# SourceFollower_SOT23_Simple.net
KiCad netlist of a schematic drawn in Altium Designer
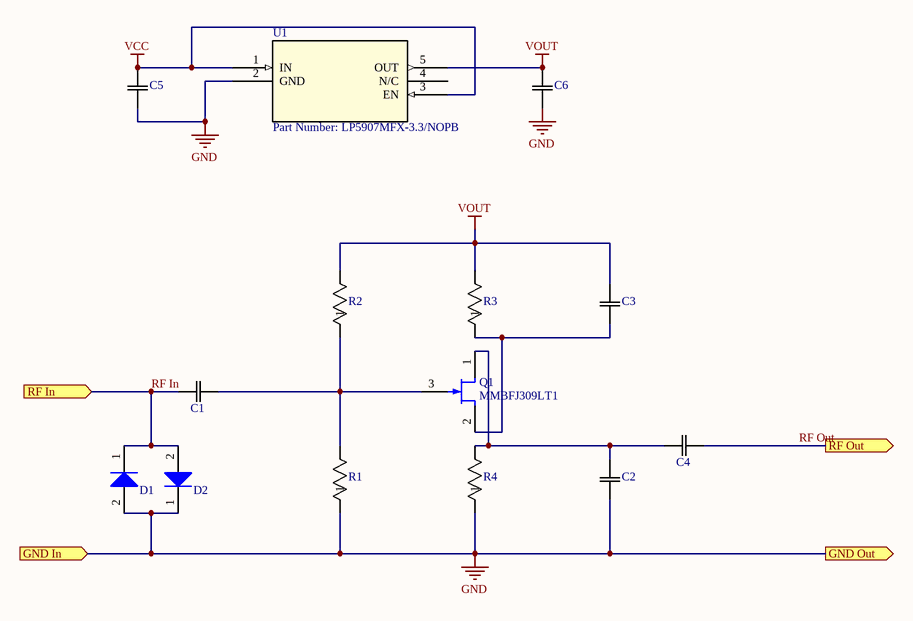
[diagram p0: SourceFollower_SOT23_Simple.SchDoc]

(export (version "E")
  (design (tool "Eeschema 10.0.6"))
  (components
    (comp (ref "C1")
      (value "Part Number: C0201C270J3GACTU")
      (footprint "C0201")
      (description "No Description Available")
      (fields
        (field (name "MANUFACTURER_PART_NUMBER") "C0201C270J3GACTU")
        (field (name "COPYRIGHT") "Copyright (C) 2018 Accelerated Designs. All rights reserved")
      )
      (libsource (lib "0201Capacitor_Yageo") (part "C0201C270J3GACTU"))
    )
    (comp (ref "C2")
      (value "Part Number: C0201C270J3GACTU")
      (footprint "C0201")
      (description "No Description Available")
      (fields
        (field (name "MANUFACTURER_PART_NUMBER") "C0201C270J3GACTU")
        (field (name "COPYRIGHT") "Copyright (C) 2018 Accelerated Designs. All rights reserved")
      )
      (libsource (lib "0201Capacitor_Yageo") (part "C0201C270J3GACTU"))
    )
    (comp (ref "C3")
      (value "Part Number: C0201C270J3GACTU")
      (footprint "C0201")
      (description "No Description Available")
      (fields
        (field (name "MANUFACTURER_PART_NUMBER") "C0201C270J3GACTU")
        (field (name "COPYRIGHT") "Copyright (C) 2018 Accelerated Designs. All rights reserved")
      )
      (libsource (lib "0201Capacitor_Yageo") (part "C0201C270J3GACTU"))
    )
    (comp (ref "C4")
      (value "Part Number: C0201C270J3GACTU")
      (footprint "C0201")
      (description "No Description Available")
      (fields
        (field (name "MANUFACTURER_PART_NUMBER") "C0201C270J3GACTU")
        (field (name "COPYRIGHT") "Copyright (C) 2018 Accelerated Designs. All rights reserved")
      )
      (libsource (lib "0201Capacitor_Yageo") (part "C0201C270J3GACTU"))
    )
    (comp (ref "C5")
      (value "Part Number: CC0402KRX7R6BB104")
      (footprint "YAG_CC0402")
      (description "No Description Available")
      (fields
        (field (name "MANUFACTURER_PART_NUMBER") "CC0402KRX7R6BB104")
        (field (name "COPYRIGHT") "Copyright (C) 2018 Accelerated Designs. All rights reserved")
      )
      (libsource (lib "0402Capacitor_Yageo") (part "CC0402KRX7R6BB10"))
    )
    (comp (ref "C6")
      (value "Part Number: CC0402KRX7R6BB104")
      (footprint "YAG_CC0402")
      (description "No Description Available")
      (fields
        (field (name "MANUFACTURER_PART_NUMBER") "CC0402KRX7R6BB104")
        (field (name "COPYRIGHT") "Copyright (C) 2018 Accelerated Designs. All rights reserved")
      )
      (libsource (lib "0402Capacitor_Yageo") (part "CC0402KRX7R6BB10"))
    )
    (comp (ref "D1")
      (value "BAT15-03W")
      (footprint "INF-SOD323_V")
      (description "Single Silicon Schottky Diode, 110 mA IF Max, SOD32, Green")
      (fields (field (name "MANUFACTURER") "Infineon"))
      (libsource (lib "Infineon_RFSchottkyDiode_SOD323") (part "BAT15-03W"))
    )
    (comp (ref "D2")
      (value "BAT15-03W")
      (footprint "INF-SOD323_V")
      (description "Single Silicon Schottky Diode, 110 mA IF Max, SOD32, Green")
      (fields (field (name "MANUFACTURER") "Infineon"))
      (libsource (lib "Infineon_RFSchottkyDiode_SOD323") (part "BAT15-03W"))
    )
    (comp (ref "Q1")
      (value "MMBFJ309LT1")
      (footprint "ONSC-SOT-23-3-318-08_V")
      (description "JFET - VHF / UHF Amplifier Transistor, N-Channel, 3-Pin SOT-23, Tape and Reel")
      (fields (field (name "MANUFACTURER") "On Semiconductor"))
      (libsource (lib "ON Semi JFETs") (part "MMBFJ309LT1"))
    )
    (comp (ref "R1")
      (value "Part Number: RC0201FR-0718KL")
      (footprint "RES_RC0201_P6XP3")
      (description "No Description Available")
      (fields
        (field (name "MANUFACTURER_PART_NUMBER") "RC0201FR-0718KL")
        (field (name "COPYRIGHT") "Copyright (C) 2018 Accelerated Designs. All rights reserved")
      )
      (libsource (lib "0201Resistor_Yageo") (part "RC0201FR-0718KL"))
    )
    (comp (ref "R2")
      (value "Part Number: RC0201FR-0718KL")
      (footprint "RES_RC0201_P6XP3")
      (description "No Description Available")
      (fields
        (field (name "MANUFACTURER_PART_NUMBER") "RC0201FR-0718KL")
        (field (name "COPYRIGHT") "Copyright (C) 2018 Accelerated Designs. All rights reserved")
      )
      (libsource (lib "0201Resistor_Yageo") (part "RC0201FR-0718KL"))
    )
    (comp (ref "R3")
      (value "Part Number: RC0201FR-0718KL")
      (footprint "RES_RC0201_P6XP3")
      (description "No Description Available")
      (fields
        (field (name "MANUFACTURER_PART_NUMBER") "RC0201FR-0718KL")
        (field (name "COPYRIGHT") "Copyright (C) 2018 Accelerated Designs. All rights reserved")
      )
      (libsource (lib "0201Resistor_Yageo") (part "RC0201FR-0718KL"))
    )
    (comp (ref "R4")
      (value "Part Number: RC0201FR-0718KL")
      (footprint "RES_RC0201_P6XP3")
      (description "No Description Available")
      (fields
        (field (name "MANUFACTURER_PART_NUMBER") "RC0201FR-0718KL")
        (field (name "COPYRIGHT") "Copyright (C) 2018 Accelerated Designs. All rights reserved")
      )
      (libsource (lib "0201Resistor_Yageo") (part "RC0201FR-0718KL"))
    )
    (comp (ref "U1")
      (value "Part Number: LP5907MFX-3.3/NOPB")
      (footprint "DBV5")
      (description "No Description Available")
      (fields
        (field (name "MANUFACTURER_PART_NUMBER") "LP5907MFX-3.3/NOPB")
        (field (name "COPYRIGHT") "Copyright (C) 2018 Accelerated Designs. All rights reserved")
      )
      (libsource (lib "TI_LDO_3V3_SOT325") (part "LP5907MFX-3.3/NO"))
    )
  )
  (nets
    (net (code "1") (name "/RF In") (class "Default")
      (node (ref "C1") (pin "1") (pinfunction "1_1") (pintype "passive"))
      (node (ref "D1") (pin "1") (pinfunction "K_1") (pintype "passive"))
      (node (ref "D2") (pin "2") (pinfunction "A_2") (pintype "passive"))
    )
    (net (code "2") (name "/RF Out") (class "Default")
      (node (ref "C4") (pin "1") (pinfunction "1_1") (pintype "passive"))
    )
    (net (code "3") (name "GND") (class "Default")
      (node (ref "C2") (pin "1") (pinfunction "1_1") (pintype "passive"))
      (node (ref "C5") (pin "1") (pinfunction "1_1") (pintype "passive"))
      (node (ref "C6") (pin "1") (pinfunction "1_1") (pintype "passive"))
      (node (ref "D1") (pin "2") (pinfunction "A_2") (pintype "passive"))
      (node (ref "D2") (pin "1") (pinfunction "K_1") (pintype "passive"))
      (node (ref "R1") (pin "1") (pinfunction "1_1") (pintype "passive"))
      (node (ref "R4") (pin "1") (pinfunction "1_1") (pintype "passive"))
      (node (ref "U1") (pin "2") (pinfunction "GND_2") (pintype "power_in"))
    )
    (net (code "4") (name "Net-(Q1-D)") (class "Default")
      (node (ref "C2") (pin "2") (pinfunction "2_2") (pintype "passive"))
      (node (ref "C4") (pin "2") (pinfunction "2_2") (pintype "passive"))
      (node (ref "Q1") (pin "1") (pinfunction "D_1") (pintype "passive"))
      (node (ref "R4") (pin "2") (pinfunction "2_2") (pintype "passive"))
    )
    (net (code "5") (name "Net-(Q1-G)") (class "Default")
      (node (ref "C1") (pin "2") (pinfunction "2_2") (pintype "passive"))
      (node (ref "Q1") (pin "3") (pinfunction "G_3") (pintype "passive"))
      (node (ref "R1") (pin "2") (pinfunction "2_2") (pintype "passive"))
      (node (ref "R2") (pin "1") (pinfunction "1_1") (pintype "passive"))
    )
    (net (code "6") (name "Net-(Q1-S)") (class "Default")
      (node (ref "C3") (pin "1") (pinfunction "1_1") (pintype "passive"))
      (node (ref "Q1") (pin "2") (pinfunction "S_2") (pintype "passive"))
      (node (ref "R3") (pin "1") (pinfunction "1_1") (pintype "passive"))
    )
    (net (code "7") (name "VCC") (class "Default")
      (node (ref "C5") (pin "2") (pinfunction "2_2") (pintype "passive"))
      (node (ref "U1") (pin "1") (pinfunction "IN_1") (pintype "input"))
      (node (ref "U1") (pin "3") (pinfunction "EN_3") (pintype "input"))
    )
    (net (code "8") (name "VOUT") (class "Default")
      (node (ref "C3") (pin "2") (pinfunction "2_2") (pintype "passive"))
      (node (ref "C6") (pin "2") (pinfunction "2_2") (pintype "passive"))
      (node (ref "R2") (pin "2") (pinfunction "2_2") (pintype "passive"))
      (node (ref "R3") (pin "2") (pinfunction "2_2") (pintype "passive"))
      (node (ref "U1") (pin "5") (pinfunction "OUT_5") (pintype "output"))
    )
    (net (code "9") (name "unconnected-(U1-N{slash}C-Pad4)") (class "Default")
      (node (ref "U1") (pin "4") (pinfunction "N/C_4") (pintype "passive"))
    )
  )
)
